# PX4AIRSPEEDv1_1.net
KiCad netlist of a schematic drawn in EAGLE
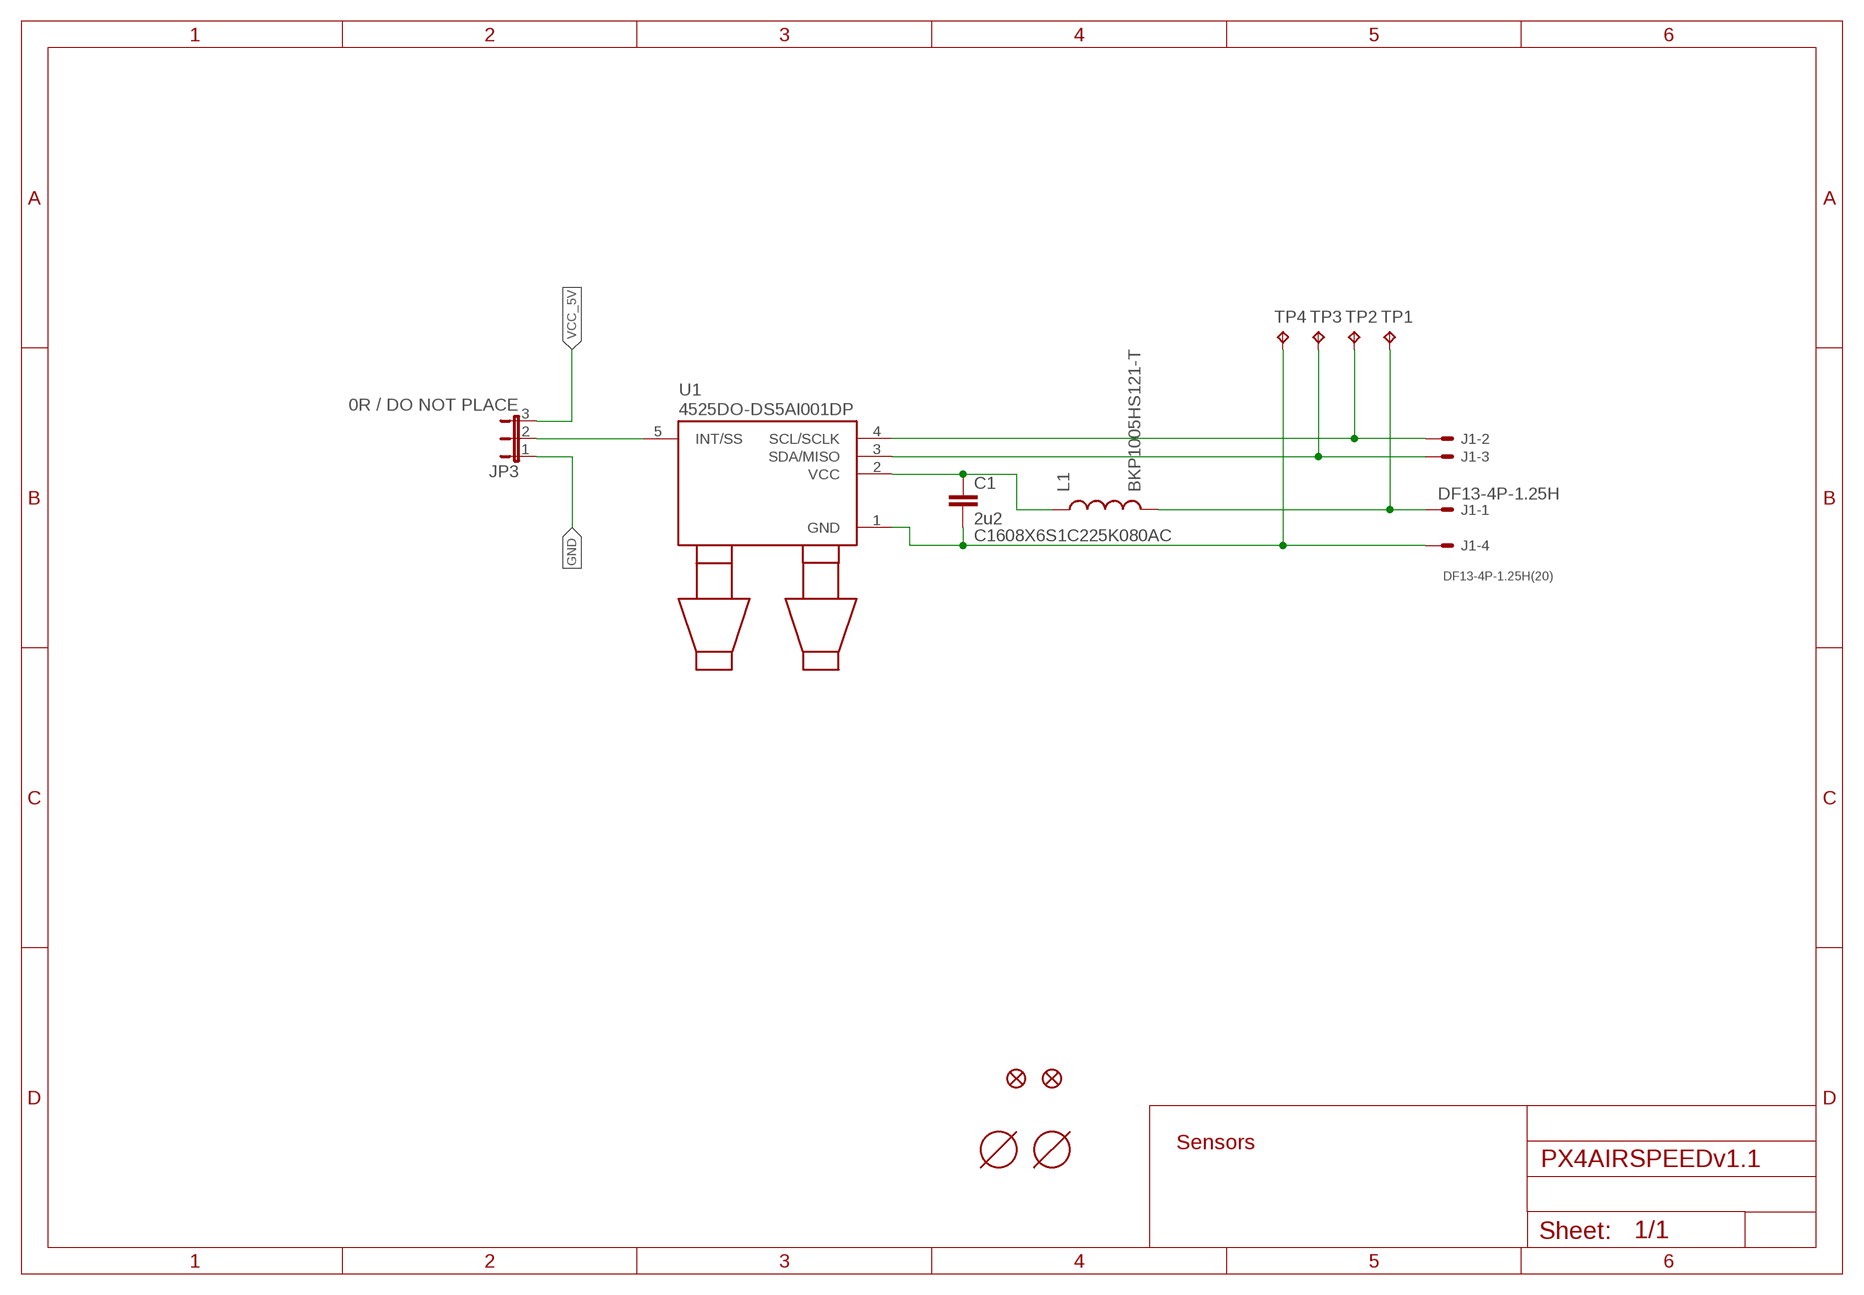
[diagram p0: schematic, sheet 1]

(export (version "E")
  (design (tool "Eeschema 10.0.6"))
  (components
    (comp (ref "C1")
      (value "2u2")
      (footprint "eagle-import:0603-CAP")
      (fields (field (name "PARTNO") "C1608X6S1C225K080AC"))
      (libsource (lib "eagle-import") (part "CAP0603"))
    )
    (comp (ref "J1")
      (value "DF13-4P-1.25H")
      (footprint "eagle-import:DF13A-4P-1.25H")
      (fields (field (name "PARTNO") "DF13-4P-1.25H(20)"))
      (libsource (lib "eagle-import") (part "DF13-4P-1.25?H"))
    )
    (comp (ref "JP1")
      (value "FIDUCIAL1X2")
      (footprint "eagle-import:FIDUCIAL-1X2")
      (libsource (lib "eagle-import") (part "FIDUCIAL1X2"))
    )
    (comp (ref "JP2")
      (value "FIDUCIAL1X2")
      (footprint "eagle-import:FIDUCIAL-1X2")
      (libsource (lib "eagle-import") (part "FIDUCIAL1X2"))
    )
    (comp (ref "JP3")
      (value "0R / DO NOT PLACE")
      (footprint "eagle-import:SJ_3_0603_PASTE1&2")
      (libsource (lib "eagle-import") (part "JUMPER-30603"))
    )
    (comp (ref "L1")
      (value "BKP1005HS121-T")
      (footprint "eagle-import:0402-IND")
      (libsource (lib "eagle-import") (part "INDUCTOR0402"))
    )
    (comp (ref "TP1")
      (value "TPTP15R")
      (footprint "eagle-import:TP15R")
      (libsource (lib "eagle-import") (part "TPTP15R"))
    )
    (comp (ref "TP2")
      (value "TPTP15R")
      (footprint "eagle-import:TP15R")
      (libsource (lib "eagle-import") (part "TPTP15R"))
    )
    (comp (ref "TP3")
      (value "TPTP15R")
      (footprint "eagle-import:TP15R")
      (libsource (lib "eagle-import") (part "TPTP15R"))
    )
    (comp (ref "TP4")
      (value "TPTP15R")
      (footprint "eagle-import:TP15R")
      (libsource (lib "eagle-import") (part "TPTP15R"))
    )
    (comp (ref "U$2")
      (value "MOUNT-HOLE3.1MM")
      (footprint "eagle-import:MOUNT-HOLE3.1")
      (libsource (lib "eagle-import") (part "MOUNT-HOLE3.1MM"))
    )
    (comp (ref "U$4")
      (value "MOUNT-HOLE3.1MM")
      (footprint "eagle-import:MOUNT-HOLE3.1")
      (libsource (lib "eagle-import") (part "MOUNT-HOLE3.1MM"))
    )
    (comp (ref "U1")
      (value "4525DO-DS5AI001DP")
      (footprint "eagle-import:4525DO-DS5AI001DP")
      (libsource (lib "eagle-import") (part "4525DO-DS5AI001DP"))
    )
  )
  (nets
    (net (code "1") (name "GND") (class "Default")
      (node (ref "C1") (pin "P$2") (pinfunction "2_P$2") (pintype "passive"))
      (node (ref "J1") (pin "4") (pinfunction "S_4") (pintype "passive"))
      (node (ref "JP3") (pin "1") (pinfunction "1_1") (pintype "passive"))
      (node (ref "TP4") (pin "TP") (pinfunction "TP_TP") (pintype "input"))
      (node (ref "U1") (pin "1") (pinfunction "GND_1") (pintype "bidirectional"))
    )
    (net (code "2") (name "Net-(J1A-S)") (class "Default")
      (node (ref "J1") (pin "1") (pinfunction "S_1") (pintype "passive"))
      (node (ref "L1") (pin "P$2") (pinfunction "2_P$2") (pintype "passive"))
      (node (ref "TP1") (pin "TP") (pinfunction "TP_TP") (pintype "input"))
    )
    (net (code "3") (name "Net-(J1B-S)") (class "Default")
      (node (ref "J1") (pin "2") (pinfunction "S_2") (pintype "passive"))
      (node (ref "TP2") (pin "TP") (pinfunction "TP_TP") (pintype "input"))
      (node (ref "U1") (pin "4") (pinfunction "SCL/SCLK_4") (pintype "bidirectional"))
    )
    (net (code "4") (name "Net-(J1C-S)") (class "Default")
      (node (ref "J1") (pin "3") (pinfunction "S_3") (pintype "passive"))
      (node (ref "TP3") (pin "TP") (pinfunction "TP_TP") (pintype "input"))
      (node (ref "U1") (pin "3") (pinfunction "SDA/MISO_3") (pintype "bidirectional"))
    )
    (net (code "5") (name "Net-(U1-INT{slash}SS)") (class "Default")
      (node (ref "JP3") (pin "2") (pinfunction "2_2") (pintype "passive"))
      (node (ref "U1") (pin "5") (pinfunction "INT/SS_5") (pintype "bidirectional"))
    )
    (net (code "6") (name "VCC_5V") (class "Default")
      (node (ref "C1") (pin "P$1") (pinfunction "1_P$1") (pintype "passive"))
      (node (ref "JP3") (pin "3") (pinfunction "3_3") (pintype "passive"))
      (node (ref "L1") (pin "P$1") (pinfunction "1_P$1") (pintype "passive"))
      (node (ref "U1") (pin "2") (pinfunction "VCC_2") (pintype "bidirectional"))
    )
  )
)
